# SLIM-PDM.net
KiCad netlist of a schematic drawn in EAGLE
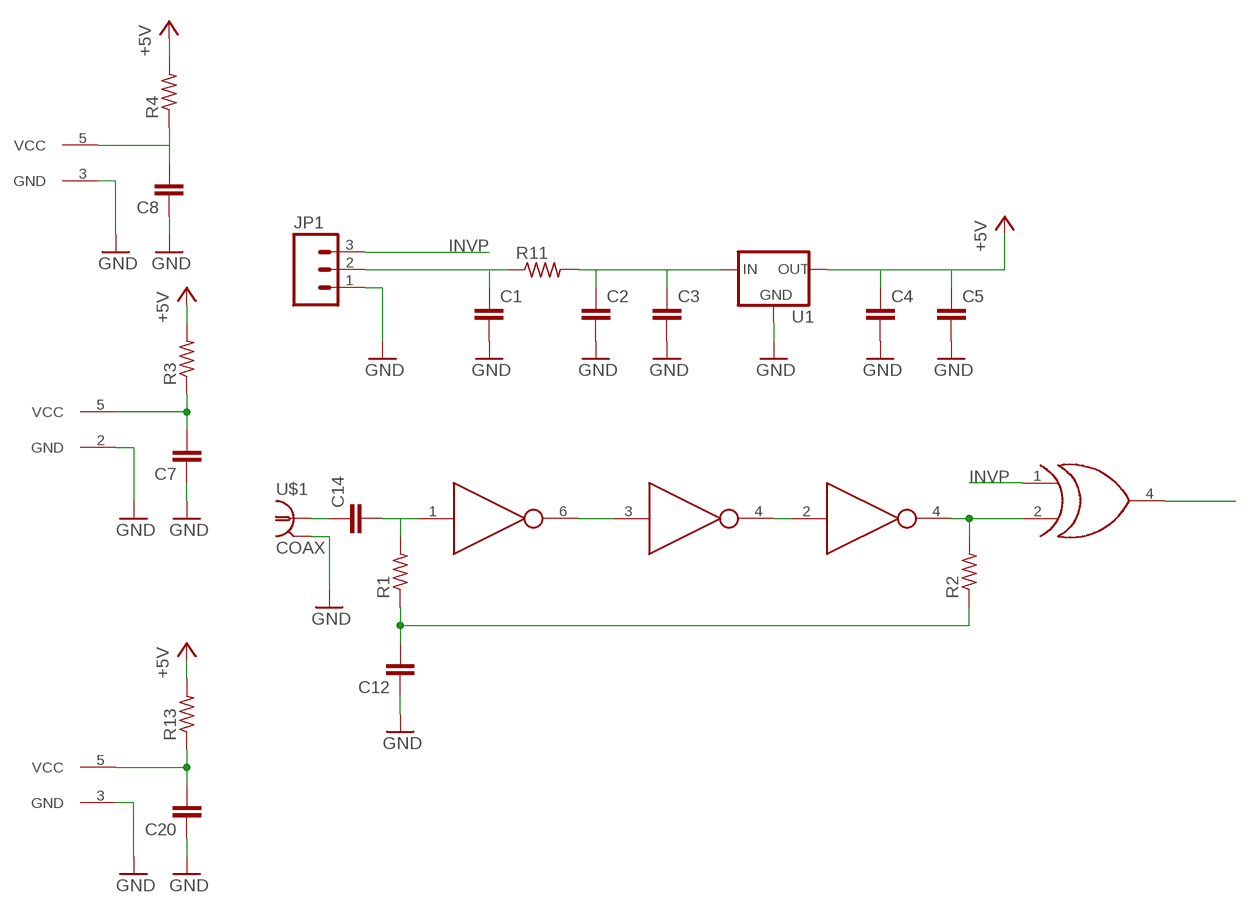
[diagram p0: schematic, sheet 1]

(export (version "E")
  (design (tool "Eeschema 10.0.6"))
  (components
    (comp (ref "C1")
      (value "C-EUC0805")
      (footprint "eagle-import:C0805")
      (libsource (lib "eagle-import") (part "C-EUC0805"))
    )
    (comp (ref "C2")
      (value "C-EUC0805")
      (footprint "eagle-import:C0805")
      (libsource (lib "eagle-import") (part "C-EUC0805"))
    )
    (comp (ref "C3")
      (value "C-EUC1206")
      (footprint "eagle-import:C1206")
      (libsource (lib "eagle-import") (part "C-EUC1206"))
    )
    (comp (ref "C4")
      (value "C-EUC0805")
      (footprint "eagle-import:C0805")
      (libsource (lib "eagle-import") (part "C-EUC0805"))
    )
    (comp (ref "C5")
      (value "C-EUC3216")
      (footprint "eagle-import:C3216")
      (libsource (lib "eagle-import") (part "C-EUC3216"))
    )
    (comp (ref "C7")
      (value "C-EUC0805")
      (footprint "eagle-import:C0805")
      (libsource (lib "eagle-import") (part "C-EUC0805"))
    )
    (comp (ref "C8")
      (value "C-EUC0805")
      (footprint "eagle-import:C0805")
      (libsource (lib "eagle-import") (part "C-EUC0805"))
    )
    (comp (ref "C12")
      (value "C-EUC0805")
      (footprint "eagle-import:C0805")
      (libsource (lib "eagle-import") (part "C-EUC0805"))
    )
    (comp (ref "C14")
      (value "C-EUC0805")
      (footprint "eagle-import:C0805")
      (libsource (lib "eagle-import") (part "C-EUC0805"))
    )
    (comp (ref "C20")
      (value "C-EUC0805")
      (footprint "eagle-import:C0805")
      (libsource (lib "eagle-import") (part "C-EUC0805"))
    )
    (comp (ref "JP1")
      (value "M03PTH")
      (footprint "eagle-import:1X03")
      (libsource (lib "eagle-import") (part "M03PTH"))
    )
    (comp (ref "R1")
      (value "R-US_R0805")
      (footprint "eagle-import:R0805")
      (libsource (lib "eagle-import") (part "R-US_R0805"))
    )
    (comp (ref "R2")
      (value "R-US_R0805")
      (footprint "eagle-import:R0805")
      (libsource (lib "eagle-import") (part "R-US_R0805"))
    )
    (comp (ref "R3")
      (value "R-US_R0805")
      (footprint "eagle-import:R0805")
      (libsource (lib "eagle-import") (part "R-US_R0805"))
    )
    (comp (ref "R4")
      (value "R-US_R0805")
      (footprint "eagle-import:R0805")
      (libsource (lib "eagle-import") (part "R-US_R0805"))
    )
    (comp (ref "R11")
      (value "R-US_R0805")
      (footprint "eagle-import:R0805")
      (libsource (lib "eagle-import") (part "R-US_R0805"))
    )
    (comp (ref "R13")
      (value "R-US_R0805")
      (footprint "eagle-import:R0805")
      (libsource (lib "eagle-import") (part "R-US_R0805"))
    )
    (comp (ref "U$1")
      (value "COAX")
      (footprint "eagle-import:SLIM_COAX_PAD")
      (libsource (lib "eagle-import") (part "COAX"))
    )
    (comp (ref "U$2")
      (value "74LVC1G86")
      (footprint "eagle-import:SOT23-5L")
      (libsource (lib "eagle-import") (part "74LVC1G86"))
    )
    (comp (ref "U1")
      (value "78MXXLSOT-89")
      (footprint "eagle-import:SOT89-BCE")
      (libsource (lib "eagle-import") (part "78MXXLSOT-89"))
    )
    (comp (ref "U2")
      (value "7WZU04")
      (footprint "eagle-import:SC70-6L")
      (libsource (lib "eagle-import") (part "7WZU04"))
    )
    (comp (ref "U3")
      (value "7SZ04")
      (footprint "eagle-import:SOT23-5L")
      (libsource (lib "eagle-import") (part "7SZ04SOT-23"))
    )
  )
  (nets
    (net (code "1") (name "+5V") (class "Default")
      (node (ref "C4") (pin "1") (pinfunction "1_1") (pintype "passive"))
      (node (ref "C5") (pin "1") (pinfunction "1_1") (pintype "passive"))
      (node (ref "R13") (pin "2") (pinfunction "2_2") (pintype "passive"))
      (node (ref "R3") (pin "2") (pinfunction "2_2") (pintype "passive"))
      (node (ref "R4") (pin "2") (pinfunction "2_2") (pintype "passive"))
      (node (ref "U1") (pin "B") (pinfunction "OUT_B") (pintype "passive"))
    )
    (net (code "2") (name "/INVP") (class "Default")
      (node (ref "JP1") (pin "3") (pinfunction "3_3") (pintype "passive"))
      (node (ref "U$2") (pin "1") (pinfunction "A_1") (pintype "bidirectional"))
    )
    (net (code "3") (name "GND") (class "Default")
      (node (ref "C1") (pin "2") (pinfunction "2_2") (pintype "passive"))
      (node (ref "C12") (pin "1") (pinfunction "1_1") (pintype "passive"))
      (node (ref "C2") (pin "2") (pinfunction "2_2") (pintype "passive"))
      (node (ref "C20") (pin "1") (pinfunction "1_1") (pintype "passive"))
      (node (ref "C3") (pin "2") (pinfunction "2_2") (pintype "passive"))
      (node (ref "C4") (pin "2") (pinfunction "2_2") (pintype "passive"))
      (node (ref "C5") (pin "2") (pinfunction "2_2") (pintype "passive"))
      (node (ref "C7") (pin "1") (pinfunction "1_1") (pintype "passive"))
      (node (ref "C8") (pin "1") (pinfunction "1_1") (pintype "passive"))
      (node (ref "JP1") (pin "1") (pinfunction "1_1") (pintype "passive"))
      (node (ref "U$1") (pin "P$2") (pinfunction "GND_P$2") (pintype "power_in"))
      (node (ref "U$2") (pin "3") (pinfunction "GND_3") (pintype "bidirectional"))
      (node (ref "U1") (pin "C") (pinfunction "GND_C") (pintype "input"))
      (node (ref "U2") (pin "2") (pinfunction "GND_2") (pintype "bidirectional"))
      (node (ref "U3") (pin "3") (pinfunction "GND_3") (pintype "bidirectional"))
    )
    (net (code "4") (name "Net-(C1-Pad1)") (class "Default")
      (node (ref "C1") (pin "1") (pinfunction "1_1") (pintype "passive"))
      (node (ref "JP1") (pin "2") (pinfunction "2_2") (pintype "passive"))
      (node (ref "R11") (pin "1") (pinfunction "1_1") (pintype "passive"))
    )
    (net (code "5") (name "Net-(C12-Pad2)") (class "Default")
      (node (ref "C12") (pin "2") (pinfunction "2_2") (pintype "passive"))
      (node (ref "R1") (pin "1") (pinfunction "1_1") (pintype "passive"))
      (node (ref "R2") (pin "1") (pinfunction "1_1") (pintype "passive"))
    )
    (net (code "6") (name "Net-(U$1-1)") (class "Default")
      (node (ref "C14") (pin "1") (pinfunction "1_1") (pintype "passive"))
      (node (ref "U$1") (pin "P$1") (pinfunction "1_P$1") (pintype "passive"))
    )
    (net (code "7") (name "Net-(U$2A-B)") (class "Default")
      (node (ref "R2") (pin "2") (pinfunction "2_2") (pintype "passive"))
      (node (ref "U$2") (pin "2") (pinfunction "B_2") (pintype "bidirectional"))
      (node (ref "U3") (pin "4") (pinfunction "OUT_4") (pintype "output"))
    )
    (net (code "8") (name "Net-(U$2B-VCC)") (class "Default")
      (node (ref "C8") (pin "2") (pinfunction "2_2") (pintype "passive"))
      (node (ref "R4") (pin "1") (pinfunction "1_1") (pintype "passive"))
      (node (ref "U$2") (pin "5") (pinfunction "VCC_5") (pintype "bidirectional"))
    )
    (net (code "9") (name "Net-(U1-IN)") (class "Default")
      (node (ref "C2") (pin "1") (pinfunction "1_1") (pintype "passive"))
      (node (ref "C3") (pin "1") (pinfunction "1_1") (pintype "passive"))
      (node (ref "R11") (pin "2") (pinfunction "2_2") (pintype "passive"))
      (node (ref "U1") (pin "E") (pinfunction "IN_E") (pintype "input"))
    )
    (net (code "10") (name "Net-(U2A-IN)") (class "Default")
      (node (ref "C14") (pin "2") (pinfunction "2_2") (pintype "passive"))
      (node (ref "R1") (pin "2") (pinfunction "2_2") (pintype "passive"))
      (node (ref "U2") (pin "1") (pinfunction "IN_1") (pintype "input"))
    )
    (net (code "11") (name "Net-(U2A-OUT)") (class "Default")
      (node (ref "U2") (pin "3") (pinfunction "IN_3") (pintype "input"))
      (node (ref "U2") (pin "6") (pinfunction "OUT_6") (pintype "output"))
    )
    (net (code "12") (name "Net-(U2B-OUT)") (class "Default")
      (node (ref "U2") (pin "4") (pinfunction "OUT_4") (pintype "output"))
      (node (ref "U3") (pin "2") (pinfunction "IN_2") (pintype "input"))
    )
    (net (code "13") (name "Net-(U2C-VCC)") (class "Default")
      (node (ref "C7") (pin "2") (pinfunction "2_2") (pintype "passive"))
      (node (ref "R3") (pin "1") (pinfunction "1_1") (pintype "passive"))
      (node (ref "U2") (pin "5") (pinfunction "VCC_5") (pintype "bidirectional"))
    )
    (net (code "14") (name "Net-(U3B-VCC)") (class "Default")
      (node (ref "C20") (pin "2") (pinfunction "2_2") (pintype "passive"))
      (node (ref "R13") (pin "1") (pinfunction "1_1") (pintype "passive"))
      (node (ref "U3") (pin "5") (pinfunction "VCC_5") (pintype "bidirectional"))
    )
    (net (code "15") (name "unconnected-(U$2A-Y-Pad4)") (class "Default")
      (node (ref "U$2") (pin "4") (pinfunction "Y_4") (pintype "bidirectional"))
    )
  )
)
